# esp-dimmer.net
KiCad netlist of a schematic drawn in EAGLE
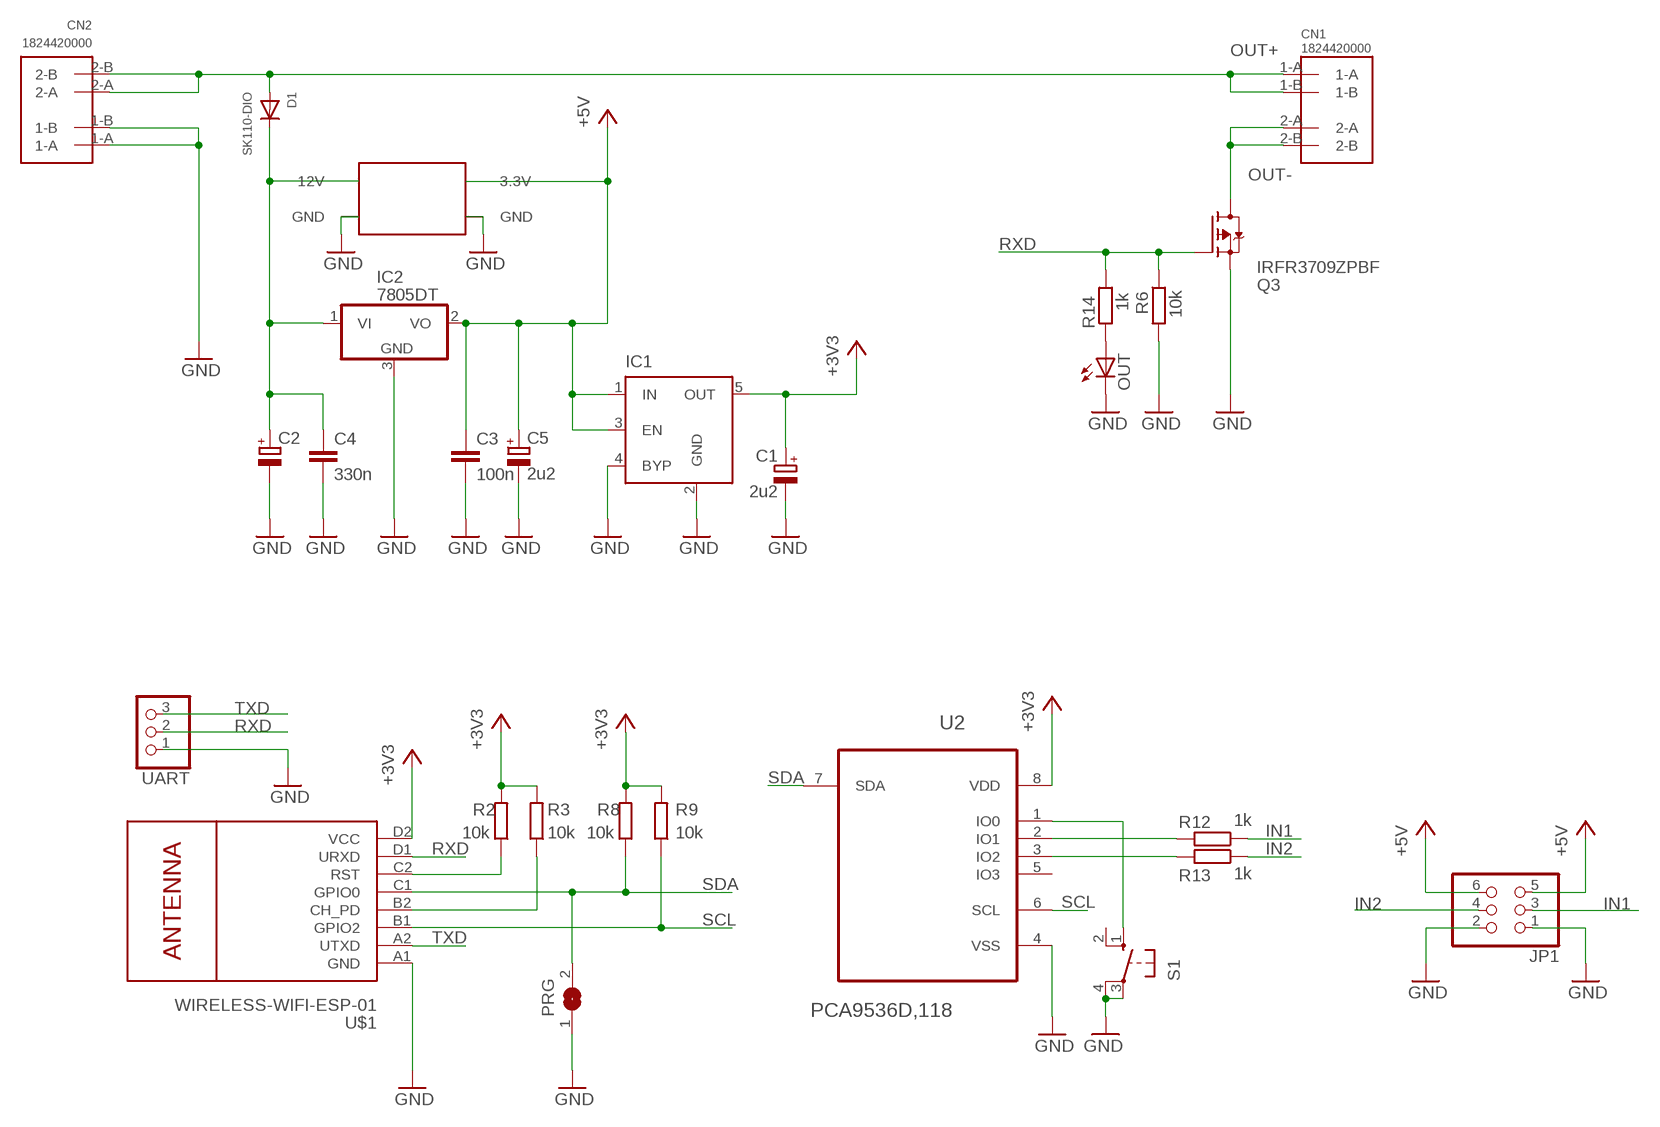
[diagram p0: schematic, sheet 1]

(export (version "E")
  (design (tool "Eeschema 10.0.6"))
  (components
    (comp (ref "C1")
      (value "2u2")
      (footprint "eagle-import:SMC_B")
      (libsource (lib "eagle-import") (part "CPOL-EUSMCB"))
    )
    (comp (ref "C2")
      (value "CPOL-EUC/6032-28R")
      (footprint "eagle-import:C_6032-28R")
      (libsource (lib "eagle-import") (part "CPOL-EUC/6032-28R"))
    )
    (comp (ref "C3")
      (value "100n")
      (footprint "eagle-import:C0805")
      (libsource (lib "eagle-import") (part "C-EUC0805"))
    )
    (comp (ref "C4")
      (value "330n")
      (footprint "eagle-import:C0805")
      (libsource (lib "eagle-import") (part "C-EUC0805"))
    )
    (comp (ref "C5")
      (value "2u2")
      (footprint "eagle-import:SMC_B")
      (libsource (lib "eagle-import") (part "CPOL-EUSMCB"))
    )
    (comp (ref "CN1")
      (value "1824420000")
      (footprint "eagle-import:1824420000")
      (fields (field (name "MF") "Weidmuller"))
      (libsource (lib "eagle-import") (part "1824420000"))
    )
    (comp (ref "CN2")
      (value "1824420000")
      (footprint "eagle-import:1824420000")
      (fields (field (name "MF") "Weidmuller"))
      (libsource (lib "eagle-import") (part "1824420000"))
    )
    (comp (ref "D1")
      (value "SK110-DIO")
      (footprint "eagle-import:SMADIODE")
      (libsource (lib "eagle-import") (part "DIODESMA"))
    )
    (comp (ref "IC1")
      (value "MIC5219XX")
      (footprint "eagle-import:SOT23-5")
      (libsource (lib "eagle-import") (part "MIC5219XX"))
    )
    (comp (ref "IC2")
      (value "7805DT")
      (footprint "eagle-import:TO252")
      (libsource (lib "eagle-import") (part "78DT05"))
    )
    (comp (ref "JP1")
      (value "PINHD-2X3")
      (footprint "eagle-import:2X03")
      (libsource (lib "eagle-import") (part "PINHD-2X3"))
    )
    (comp (ref "OUT")
      (value "LEDCHIPLED_0805")
      (footprint "eagle-import:CHIPLED_0805")
      (libsource (lib "eagle-import") (part "LEDCHIPLED_0805"))
    )
    (comp (ref "PRG") (value "SJ") (footprint "eagle-import:SJ") (libsource (lib "eagle-import") (part "SJ")))
    (comp (ref "Q3")
      (value "IRFR3709ZPBF")
      (footprint "eagle-import:TO252")
      (libsource (lib "eagle-import") (part "SPD30P06PTO252"))
    )
    (comp (ref "R2")
      (value "10k")
      (footprint "eagle-import:R0805")
      (libsource (lib "eagle-import") (part "R-EU_R0805"))
    )
    (comp (ref "R3")
      (value "10k")
      (footprint "eagle-import:R0805")
      (libsource (lib "eagle-import") (part "R-EU_R0805"))
    )
    (comp (ref "R6")
      (value "10k")
      (footprint "eagle-import:R0805")
      (libsource (lib "eagle-import") (part "R-EU_R0805"))
    )
    (comp (ref "R8")
      (value "10k")
      (footprint "eagle-import:R0805")
      (libsource (lib "eagle-import") (part "R-EU_R0805"))
    )
    (comp (ref "R9")
      (value "10k")
      (footprint "eagle-import:R0805")
      (libsource (lib "eagle-import") (part "R-EU_R0805"))
    )
    (comp (ref "R12")
      (value "1k")
      (footprint "eagle-import:R0805")
      (libsource (lib "eagle-import") (part "R-EU_R0805"))
    )
    (comp (ref "R13")
      (value "1k")
      (footprint "eagle-import:R0805")
      (libsource (lib "eagle-import") (part "R-EU_R0805"))
    )
    (comp (ref "R14")
      (value "1k")
      (footprint "eagle-import:R0805")
      (libsource (lib "eagle-import") (part "R-EU_R0805"))
    )
    (comp (ref "S1")
      (value "10-XX")
      (footprint "eagle-import:B3F-10XX")
      (fields (field (name "MPN") "B3F-1000"))
      (libsource (lib "eagle-import") (part "10-XX"))
    )
    (comp (ref "U$1")
      (value "WIRELESS-WIFI-ESP-01")
      (footprint "eagle-import:WIRELESS-WIFI-ESP-01")
      (libsource (lib "eagle-import") (part "WIRELESS-WIFI-ESP-01"))
    )
    (comp (ref "U$2")
      (value "MP2307-MINI-360")
      (footprint "eagle-import:MP2307-MINI-360")
      (libsource (lib "eagle-import") (part "MP2307-MINI-360"))
    )
    (comp (ref "U2")
      (value "PCA9536D,118")
      (footprint "eagle-import:SOIC127P600X175-8N")
      (fields (field (name "MF") "NXP USA"))
      (libsource (lib "eagle-import") (part "PCA9536D,118"))
    )
    (comp (ref "UART")
      (value "PINHD-1X3")
      (footprint "eagle-import:1X03")
      (libsource (lib "eagle-import") (part "PINHD-1X3"))
    )
  )
  (nets
    (net (code "1") (name "+3V3") (class "Default")
      (node (ref "C1") (pin "+") (pinfunction "+_+") (pintype "passive"))
      (node (ref "IC1") (pin "5") (pinfunction "OUT_5") (pintype "output"))
      (node (ref "R2") (pin "2") (pinfunction "2_2") (pintype "passive"))
      (node (ref "R3") (pin "2") (pinfunction "2_2") (pintype "passive"))
      (node (ref "R8") (pin "2") (pinfunction "2_2") (pintype "passive"))
      (node (ref "R9") (pin "2") (pinfunction "2_2") (pintype "passive"))
      (node (ref "U$1") (pin "D2") (pinfunction "VCC_D2") (pintype "power_in"))
      (node (ref "U2") (pin "8") (pinfunction "VDD_8") (pintype "power_in"))
    )
    (net (code "2") (name "+5V") (class "Default")
      (node (ref "C3") (pin "1") (pinfunction "1_1") (pintype "passive"))
      (node (ref "C5") (pin "+") (pinfunction "+_+") (pintype "passive"))
      (node (ref "IC1") (pin "1") (pinfunction "IN_1") (pintype "input"))
      (node (ref "IC1") (pin "3") (pinfunction "EN_3") (pintype "input"))
      (node (ref "IC2") (pin "2") (pinfunction "VO_2") (pintype "passive"))
      (node (ref "JP1") (pin "5") (pinfunction "5_5") (pintype "passive"))
      (node (ref "JP1") (pin "6") (pinfunction "6_6") (pintype "passive"))
      (node (ref "U$2") (pin "3.3V") (pinfunction "3.3V_3.3V") (pintype "power_in"))
    )
    (net (code "3") (name "/IN1") (class "Default")
      (node (ref "JP1") (pin "3") (pinfunction "3_3") (pintype "passive"))
      (node (ref "R12") (pin "1") (pinfunction "1_1") (pintype "passive"))
    )
    (net (code "4") (name "/IN2") (class "Default")
      (node (ref "JP1") (pin "4") (pinfunction "4_4") (pintype "passive"))
      (node (ref "R13") (pin "1") (pinfunction "1_1") (pintype "passive"))
    )
    (net (code "5") (name "/OUT+") (class "Default")
      (node (ref "CN1") (pin "1-A") (pinfunction "1-A_1-A") (pintype "bidirectional"))
      (node (ref "CN1") (pin "1-B") (pinfunction "1-B_1-B") (pintype "bidirectional"))
      (node (ref "CN2") (pin "2-A") (pinfunction "2-A_2-A") (pintype "bidirectional"))
      (node (ref "CN2") (pin "2-B") (pinfunction "2-B_2-B") (pintype "bidirectional"))
      (node (ref "D1") (pin "A") (pinfunction "A_A") (pintype "passive"))
    )
    (net (code "6") (name "/OUT-") (class "Default")
      (node (ref "CN1") (pin "2-A") (pinfunction "2-A_2-A") (pintype "bidirectional"))
      (node (ref "CN1") (pin "2-B") (pinfunction "2-B_2-B") (pintype "bidirectional"))
      (node (ref "Q3") (pin "3") (pinfunction "D_3") (pintype "passive"))
    )
    (net (code "7") (name "/RXD") (class "Default")
      (node (ref "Q3") (pin "1") (pinfunction "G_1") (pintype "passive"))
      (node (ref "R14") (pin "2") (pinfunction "2_2") (pintype "passive"))
      (node (ref "R6") (pin "1") (pinfunction "1_1") (pintype "passive"))
      (node (ref "U$1") (pin "D1") (pinfunction "URXD_D1") (pintype "bidirectional"))
      (node (ref "UART") (pin "2") (pinfunction "2_2") (pintype "passive"))
    )
    (net (code "8") (name "/SCL") (class "Default")
      (node (ref "R9") (pin "1") (pinfunction "1_1") (pintype "passive"))
      (node (ref "U$1") (pin "B1") (pinfunction "GPIO2_B1") (pintype "bidirectional"))
      (node (ref "U2") (pin "6") (pinfunction "SCL_6") (pintype "input"))
    )
    (net (code "9") (name "/SDA") (class "Default")
      (node (ref "PRG") (pin "2") (pinfunction "2_2") (pintype "passive"))
      (node (ref "R8") (pin "1") (pinfunction "1_1") (pintype "passive"))
      (node (ref "U$1") (pin "C1") (pinfunction "GPIO0_C1") (pintype "bidirectional"))
      (node (ref "U2") (pin "7") (pinfunction "SDA_7") (pintype "bidirectional"))
    )
    (net (code "10") (name "/TXD") (class "Default")
      (node (ref "U$1") (pin "A2") (pinfunction "UTXD_A2") (pintype "bidirectional"))
      (node (ref "UART") (pin "3") (pinfunction "3_3") (pintype "passive"))
    )
    (net (code "11") (name "GND") (class "Default")
      (node (ref "C1") (pin "-") (pinfunction "-_-") (pintype "passive"))
      (node (ref "C2") (pin "-") (pinfunction "-_-") (pintype "passive"))
      (node (ref "C3") (pin "2") (pinfunction "2_2") (pintype "passive"))
      (node (ref "C4") (pin "2") (pinfunction "2_2") (pintype "passive"))
      (node (ref "C5") (pin "-") (pinfunction "-_-") (pintype "passive"))
      (node (ref "CN2") (pin "1-A") (pinfunction "1-A_1-A") (pintype "bidirectional"))
      (node (ref "CN2") (pin "1-B") (pinfunction "1-B_1-B") (pintype "bidirectional"))
      (node (ref "IC1") (pin "2") (pinfunction "GND_2") (pintype "power_in"))
      (node (ref "IC1") (pin "4") (pinfunction "BYP_4") (pintype "passive"))
      (node (ref "IC2") (pin "3") (pinfunction "GND_3") (pintype "passive"))
      (node (ref "JP1") (pin "1") (pinfunction "1_1") (pintype "passive"))
      (node (ref "JP1") (pin "2") (pinfunction "2_2") (pintype "passive"))
      (node (ref "OUT") (pin "C") (pinfunction "C_C") (pintype "passive"))
      (node (ref "PRG") (pin "1") (pinfunction "1_1") (pintype "passive"))
      (node (ref "Q3") (pin "2") (pinfunction "S_2") (pintype "passive"))
      (node (ref "R6") (pin "2") (pinfunction "2_2") (pintype "passive"))
      (node (ref "S1") (pin "3") (pinfunction "P_3") (pintype "passive"))
      (node (ref "S1") (pin "4") (pinfunction "P1_4") (pintype "passive"))
      (node (ref "U$1") (pin "A1") (pinfunction "GND_A1") (pintype "power_in"))
      (node (ref "U$2") (pin "GND@1") (pinfunction "GND_GND@1") (pintype "power_in"))
      (node (ref "U$2") (pin "GND@2") (pinfunction "GND_GND@2") (pintype "power_in"))
      (node (ref "U2") (pin "4") (pinfunction "VSS_4") (pintype "power_in"))
      (node (ref "UART") (pin "1") (pinfunction "1_1") (pintype "passive"))
    )
    (net (code "12") (name "Net-(IC2-VI)") (class "Default")
      (node (ref "C2") (pin "+") (pinfunction "+_+") (pintype "passive"))
      (node (ref "C4") (pin "1") (pinfunction "1_1") (pintype "passive"))
      (node (ref "D1") (pin "C") (pinfunction "C_C") (pintype "passive"))
      (node (ref "IC2") (pin "1") (pinfunction "VI_1") (pintype "input"))
      (node (ref "U$2") (pin "12V") (pinfunction "12V_12V") (pintype "power_in"))
    )
    (net (code "13") (name "Net-(OUT-PadA)") (class "Default")
      (node (ref "OUT") (pin "A") (pinfunction "A_A") (pintype "passive"))
      (node (ref "R14") (pin "1") (pinfunction "1_1") (pintype "passive"))
    )
    (net (code "14") (name "Net-(S1-S)") (class "Default")
      (node (ref "S1") (pin "1") (pinfunction "S_1") (pintype "passive"))
      (node (ref "U2") (pin "1") (pinfunction "IO0_1") (pintype "bidirectional"))
    )
    (net (code "15") (name "Net-(U$1-CH_PD)") (class "Default")
      (node (ref "R3") (pin "1") (pinfunction "1_1") (pintype "passive"))
      (node (ref "U$1") (pin "B2") (pinfunction "CH_PD_B2") (pintype "bidirectional"))
    )
    (net (code "16") (name "Net-(U$1-RST)") (class "Default")
      (node (ref "R2") (pin "1") (pinfunction "1_1") (pintype "passive"))
      (node (ref "U$1") (pin "C2") (pinfunction "RST_C2") (pintype "bidirectional"))
    )
    (net (code "17") (name "Net-(U2-IO1)") (class "Default")
      (node (ref "R12") (pin "2") (pinfunction "2_2") (pintype "passive"))
      (node (ref "U2") (pin "2") (pinfunction "IO1_2") (pintype "bidirectional"))
    )
    (net (code "18") (name "Net-(U2-IO2)") (class "Default")
      (node (ref "R13") (pin "2") (pinfunction "2_2") (pintype "passive"))
      (node (ref "U2") (pin "3") (pinfunction "IO2_3") (pintype "bidirectional"))
    )
    (net (code "19") (name "unconnected-(S1-S1-Pad2)") (class "Default")
      (node (ref "S1") (pin "2") (pinfunction "S1_2") (pintype "passive"))
    )
    (net (code "20") (name "unconnected-(U2-IO3-Pad5)") (class "Default")
      (node (ref "U2") (pin "5") (pinfunction "IO3_5") (pintype "bidirectional"))
    )
  )
)
